# Board2.net
KiCad netlist of a schematic drawn in Altium Designer
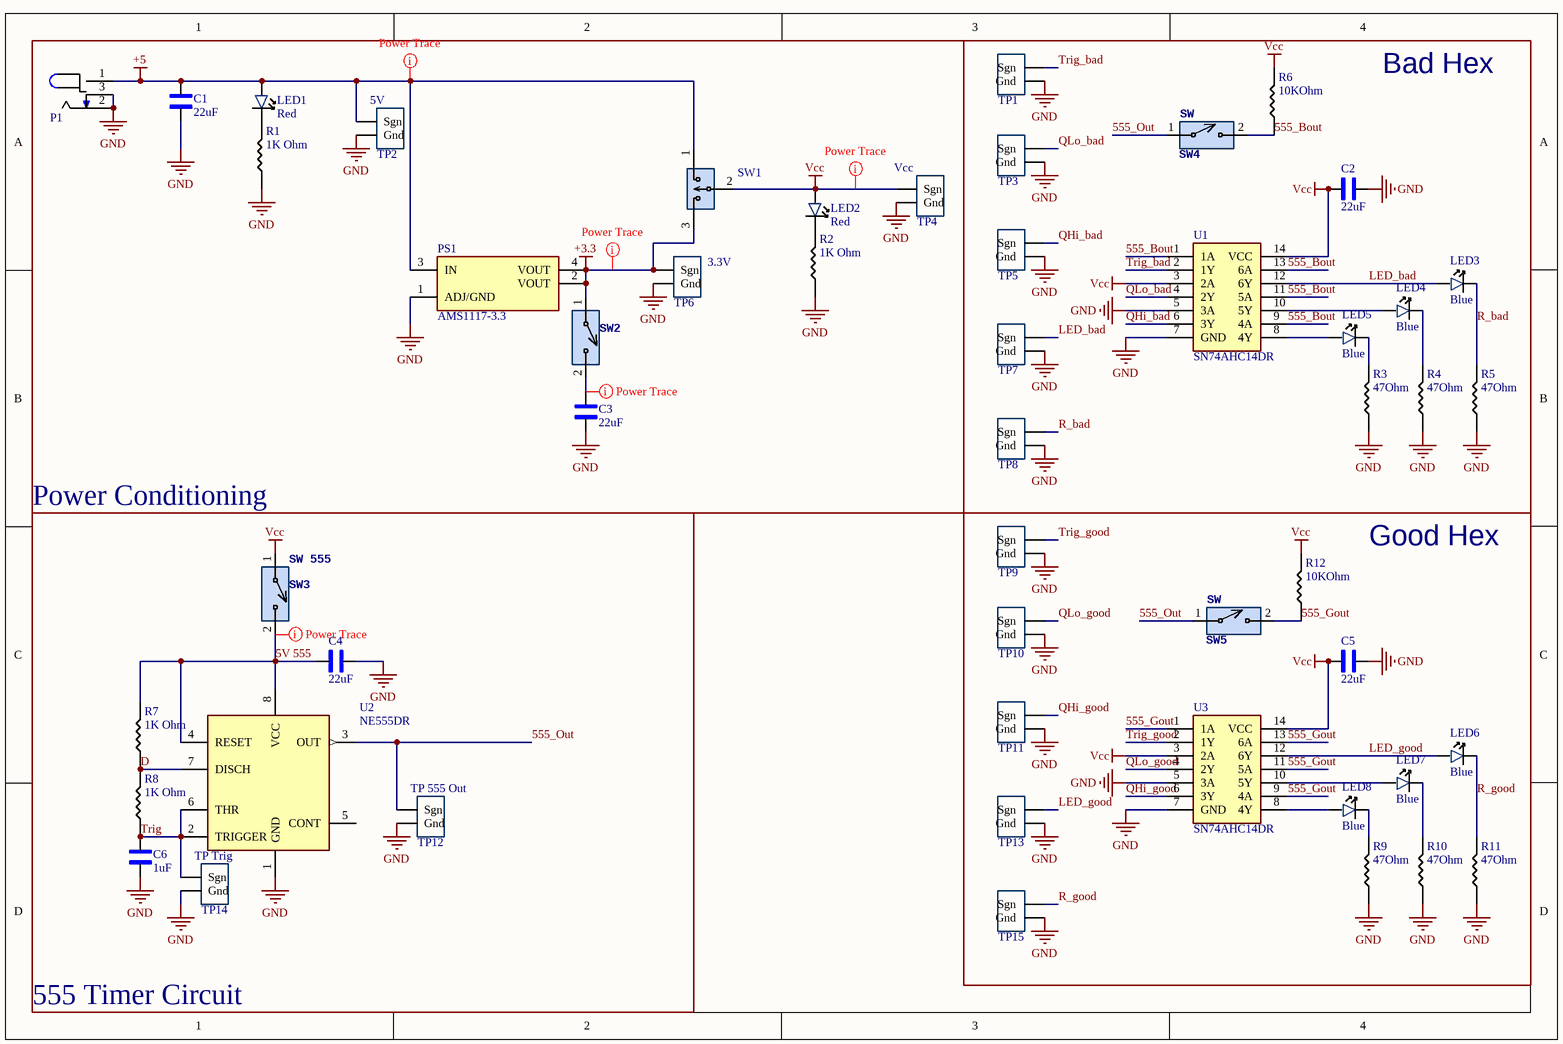
[diagram p0: Board2.SchDoc]

(export (version "E")
  (design (tool "Eeschema 10.0.6"))
  (components
    (comp (ref "C1")
      (value "22uF")
      (footprint "1206_Passive_Capacitor")
      (description "22uF ±10% 25V X5R 1206 Multilayer Ceramic Capacitors MLCC - SMD/SMT RoHS")
      (fields (field (name "MFR PART #") "CL31A226KAHNNNE") (field (name "LCSC PART#") "C12891"))
      (libsource (lib "ECEN5730Lib_2023_01_DS") (part "C_22uF_1206"))
    )
    (comp (ref "C2")
      (value "22uF")
      (footprint "1206_Passive_Capacitor")
      (description "22uF ±10% 25V X5R 1206 Multilayer Ceramic Capacitors MLCC - SMD/SMT RoHS")
      (fields (field (name "MFR PART #") "CL31A226KAHNNNE") (field (name "LCSC PART#") "C12891"))
      (libsource (lib "ECEN5730Lib_2023_01_DS") (part "C_22uF_1206"))
    )
    (comp (ref "C3")
      (value "22uF")
      (footprint "1206_Passive_Capacitor")
      (description "22uF ±10% 25V X5R 1206 Multilayer Ceramic Capacitors MLCC - SMD/SMT RoHS")
      (fields (field (name "MFR PART #") "CL31A226KAHNNNE") (field (name "LCSC PART#") "C12891"))
      (libsource (lib "ECEN5730Lib_2023_01_DS") (part "C_22uF_1206"))
    )
    (comp (ref "C4")
      (value "22uF")
      (footprint "1206_Passive_Capacitor")
      (description "22uF ±10% 25V X5R 1206 Multilayer Ceramic Capacitors MLCC - SMD/SMT RoHS")
      (fields (field (name "MFR PART #") "CL31A226KAHNNNE") (field (name "LCSC PART#") "C12891"))
      (libsource (lib "ECEN5730Lib_2023_01_DS") (part "C_22uF_1206"))
    )
    (comp (ref "C5")
      (value "22uF")
      (footprint "1206_Passive_Capacitor")
      (description "22uF ±10% 25V X5R 1206 Multilayer Ceramic Capacitors MLCC - SMD/SMT RoHS")
      (fields (field (name "MFR PART #") "CL31A226KAHNNNE") (field (name "LCSC PART#") "C12891"))
      (libsource (lib "ECEN5730Lib_2023_01_DS") (part "C_22uF_1206"))
    )
    (comp (ref "C6")
      (value "1uF")
      (footprint "1206_Passive_Capacitor")
      (description "MULTILAYER CERAMIC CAPACITORS MLCC - SMD/SMT 1UF 50V 1206 ROHS")
      (fields (field (name "MFR PART #") "CL31B105KBHNNNE") (field (name "LCSC PART#") "C1848"))
      (libsource (lib "ECEN5730Lib_2023_01_DS") (part "C_1uF_1206"))
    )
    (comp (ref "LED1")
      (value "Red")
      (footprint "LED_1206")
      (description "Red 621~631nm 1206 Light Emitting Diodes (LED) RoHS")
      (fields (field (name "MFR PART #") "15-21/R6C-FQ1R1B/2T") (field (name "LCSC PART#") "C93133"))
      (libsource (lib "ECEN5730Lib_2023_01_DS") (part "LED_RED_1206"))
    )
    (comp (ref "LED2")
      (value "Red")
      (footprint "LED_1206")
      (description "Red 621~631nm 1206 Light Emitting Diodes (LED) RoHS")
      (fields (field (name "MFR PART #") "15-21/R6C-FQ1R1B/2T") (field (name "LCSC PART#") "C93133"))
      (libsource (lib "ECEN5730Lib_2023_01_DS") (part "LED_RED_1206"))
    )
    (comp (ref "LED3")
      (value "Blue")
      (footprint "LED_1206")
      (description "blue 1206  Light Emitting Diodes (LED) ROHS")
      (fields (field (name "MFR PART #") "NCD1206B1") (field (name "LCSC PART#") "C130717"))
      (libsource (lib "ECEN5730Lib_2023_01_DS") (part "LED_BLUE_1206"))
    )
    (comp (ref "LED4")
      (value "Blue")
      (footprint "LED_1206")
      (description "blue 1206  Light Emitting Diodes (LED) ROHS")
      (fields (field (name "MFR PART #") "NCD1206B1") (field (name "LCSC PART#") "C130717"))
      (libsource (lib "ECEN5730Lib_2023_01_DS") (part "LED_BLUE_1206"))
    )
    (comp (ref "LED5")
      (value "Blue")
      (footprint "LED_1206")
      (description "blue 1206  Light Emitting Diodes (LED) ROHS")
      (fields (field (name "MFR PART #") "NCD1206B1") (field (name "LCSC PART#") "C130717"))
      (libsource (lib "ECEN5730Lib_2023_01_DS") (part "LED_BLUE_1206"))
    )
    (comp (ref "LED6")
      (value "Blue")
      (footprint "LED_1206")
      (description "blue 1206  Light Emitting Diodes (LED) ROHS")
      (fields (field (name "MFR PART #") "NCD1206B1") (field (name "LCSC PART#") "C130717"))
      (libsource (lib "ECEN5730Lib_2023_01_DS") (part "LED_BLUE_1206"))
    )
    (comp (ref "LED7")
      (value "Blue")
      (footprint "LED_1206")
      (description "blue 1206  Light Emitting Diodes (LED) ROHS")
      (fields (field (name "MFR PART #") "NCD1206B1") (field (name "LCSC PART#") "C130717"))
      (libsource (lib "ECEN5730Lib_2023_01_DS") (part "LED_BLUE_1206"))
    )
    (comp (ref "LED8")
      (value "Blue")
      (footprint "LED_1206")
      (description "blue 1206  Light Emitting Diodes (LED) ROHS")
      (fields (field (name "MFR PART #") "NCD1206B1") (field (name "LCSC PART#") "C130717"))
      (libsource (lib "ECEN5730Lib_2023_01_DS") (part "LED_BLUE_1206"))
    )
    (comp (ref "P1")
      (value "Power Jack")
      (footprint "Power_Jack")
      (description "Power Barrel Connector Jack 2.10mm ID (0.083\"), 5.50mm OD (0.217\") Through Hole, Right Angle")
      (fields (field (name "MFR PART #") "PJ-102A") (field (name "LCSC PART#") "C136744"))
      (libsource (lib "ECEN5730Lib_2023_01_DS") (part "P_Power Jack"))
    )
    (comp (ref "PS1")
      (value "AMS1117-3.3")
      (footprint "LDO")
      (description "LOW DROPOUT REGULATORS(LDO) POSITIVE FIXED 1.3V @ 800MA 15V 3.3V 1A SOT-223 ROHS")
      (fields (field (name "LCSC PART#") "C6186"))
      (libsource (lib "ECEN5730Lib_2023_01_DS") (part "PS_AMS_LDO_3v3"))
    )
    (comp (ref "R1")
      (value "1K Ohm")
      (footprint "1206_Passive_Resitor")
      (description "CHIP RESISTOR - SURFACE MOUNT 1KOHMS ±1% 1/4W 1206 ROHS")
      (fields (field (name "MFR PART #") "RNCP1206FTD1K00CT") (field (name "LCSC PART#") "C4410"))
      (libsource (lib "ECEN5730Lib_2023_01_DS") (part "R_1K_1206"))
    )
    (comp (ref "R2")
      (value "1K Ohm")
      (footprint "1206_Passive_Resitor")
      (description "CHIP RESISTOR - SURFACE MOUNT 1KOHMS ±1% 1/4W 1206 ROHS")
      (fields (field (name "MFR PART #") "RNCP1206FTD1K00CT") (field (name "LCSC PART#") "C4410"))
      (libsource (lib "ECEN5730Lib_2023_01_DS") (part "R_1K_1206"))
    )
    (comp (ref "R3")
      (value "47Ohm")
      (footprint "1206_Passive_Resitor")
      (description "47Ω ±5% 0.25W ±200ppm/℃ 1206 Chip Resistor - Surface Mount RoHS")
      (fields (field (name "MFR PART #") "1206W4J0470T5E") (field (name "LCSC PART#") "C25384"))
      (libsource (lib "ECEN5730Lib_2023_01_DS") (part "R_47Ohm_1206"))
    )
    (comp (ref "R4")
      (value "47Ohm")
      (footprint "1206_Passive_Resitor")
      (description "47Ω ±5% 0.25W ±200ppm/℃ 1206 Chip Resistor - Surface Mount RoHS")
      (fields (field (name "MFR PART #") "1206W4J0470T5E") (field (name "LCSC PART#") "C25384"))
      (libsource (lib "ECEN5730Lib_2023_01_DS") (part "R_47Ohm_1206"))
    )
    (comp (ref "R5")
      (value "47Ohm")
      (footprint "1206_Passive_Resitor")
      (description "47Ω ±5% 0.25W ±200ppm/℃ 1206 Chip Resistor - Surface Mount RoHS")
      (fields (field (name "MFR PART #") "1206W4J0470T5E") (field (name "LCSC PART#") "C25384"))
      (libsource (lib "ECEN5730Lib_2023_01_DS") (part "R_47Ohm_1206"))
    )
    (comp (ref "R6")
      (value "10KOhm")
      (footprint "1206_Passive_Resitor")
      (description "10 kOhms ±5% 0.25W, 1/4W Chip Resistor 1206 (3216 Metric) Automotive AEC-Q200 Thick Film")
      (fields (field (name "MFR PART #") "RMCF1206FT10K0") (field (name "LCSC PART#") "C17902"))
      (libsource (lib "ECEN5730Lib_2023_01_DS") (part "R_10KOhm_1206"))
    )
    (comp (ref "R7")
      (value "1K Ohm")
      (footprint "1206_Passive_Resitor")
      (description "CHIP RESISTOR - SURFACE MOUNT 1KOHMS ±1% 1/4W 1206 ROHS")
      (fields (field (name "MFR PART #") "RNCP1206FTD1K00CT") (field (name "LCSC PART#") "C4410"))
      (libsource (lib "ECEN5730Lib_2023_01_DS") (part "R_1K_1206"))
    )
    (comp (ref "R8")
      (value "1K Ohm")
      (footprint "1206_Passive_Resitor")
      (description "CHIP RESISTOR - SURFACE MOUNT 1KOHMS ±1% 1/4W 1206 ROHS")
      (fields (field (name "MFR PART #") "RNCP1206FTD1K00CT") (field (name "LCSC PART#") "C4410"))
      (libsource (lib "ECEN5730Lib_2023_01_DS") (part "R_1K_1206"))
    )
    (comp (ref "R9")
      (value "47Ohm")
      (footprint "1206_Passive_Resitor")
      (description "47Ω ±5% 0.25W ±200ppm/℃ 1206 Chip Resistor - Surface Mount RoHS")
      (fields (field (name "MFR PART #") "1206W4J0470T5E") (field (name "LCSC PART#") "C25384"))
      (libsource (lib "ECEN5730Lib_2023_01_DS") (part "R_47Ohm_1206"))
    )
    (comp (ref "R10")
      (value "47Ohm")
      (footprint "1206_Passive_Resitor")
      (description "47Ω ±5% 0.25W ±200ppm/℃ 1206 Chip Resistor - Surface Mount RoHS")
      (fields (field (name "MFR PART #") "1206W4J0470T5E") (field (name "LCSC PART#") "C25384"))
      (libsource (lib "ECEN5730Lib_2023_01_DS") (part "R_47Ohm_1206"))
    )
    (comp (ref "R11")
      (value "47Ohm")
      (footprint "1206_Passive_Resitor")
      (description "47Ω ±5% 0.25W ±200ppm/℃ 1206 Chip Resistor - Surface Mount RoHS")
      (fields (field (name "MFR PART #") "1206W4J0470T5E") (field (name "LCSC PART#") "C25384"))
      (libsource (lib "ECEN5730Lib_2023_01_DS") (part "R_47Ohm_1206"))
    )
    (comp (ref "R12")
      (value "10KOhm")
      (footprint "1206_Passive_Resitor")
      (description "10 kOhms ±5% 0.25W, 1/4W Chip Resistor 1206 (3216 Metric) Automotive AEC-Q200 Thick Film")
      (fields (field (name "MFR PART #") "RMCF1206FT10K0") (field (name "LCSC PART#") "C17902"))
      (libsource (lib "ECEN5730Lib_2023_01_DS") (part "R_10KOhm_1206"))
    )
    (comp (ref "SW1")
      (value "PREC003SAAN-RC")
      (footprint "3_PIN_100mil")
      (description "Connector Header Through Hole 3 position 0.100\" (2.54mm)")
      (fields (field (name "LCSC PART#") "C49257"))
      (libsource (lib "ECEN5730Lib_2023_01_DS") (part "SW_3Pin_100mil_Switch"))
    )
    (comp (ref "SW2")
      (value "SW_2Pin_100mil_Switch")
      (footprint "2Pin-Header-Conn")
      (description "2Pin Header")
      (fields (field (name "LCSC PART#") "C124375"))
      (libsource (lib "") (part "SW_2Pin_100mil_Switch_1"))
    )
    (comp (ref "SW3")
      (value "SW 555")
      (footprint "2Pin-Header-Conn")
      (description "2Pin Header")
      (fields (field (name "LCSC PART#") "C124375"))
      (libsource (lib "") (part "SW_2Pin_100mil_Switch_1"))
    )
    (comp (ref "SW4")
      (value "SW")
      (footprint "2Pin-Header-Conn")
      (description "2Pin Header")
      (fields (field (name "LCSC PART#") "C124375"))
      (libsource (lib "ECEN5730Lib_2023_01_DS") (part "SW_2Pin_100mil_Switch"))
    )
    (comp (ref "SW5")
      (value "SW")
      (footprint "2Pin-Header-Conn")
      (description "2Pin Header")
      (fields (field (name "LCSC PART#") "C124375"))
      (libsource (lib "ECEN5730Lib_2023_01_DS") (part "SW_2Pin_100mil_Switch"))
    )
    (comp (ref "TP1")
      (value "10x Probe TP")
      (footprint "TP10x_Probe")
      (description "Test Point 300 mil centers")
      (libsource (lib "") (part "TP_10x_Probe_1"))
    )
    (comp (ref "TP2")
      (value "5V")
      (footprint "TP10x_Probe")
      (description "Test Point 300 mil centers")
      (libsource (lib "ECEN5730Lib_2023_01_DS") (part "TP_10x_Probe"))
    )
    (comp (ref "TP3")
      (value "10x Probe TP")
      (footprint "TP10x_Probe")
      (description "Test Point 300 mil centers")
      (libsource (lib "") (part "TP_10x_Probe_1"))
    )
    (comp (ref "TP4")
      (value "Vcc")
      (footprint "TP10x_Probe")
      (description "Test Point 300 mil centers")
      (libsource (lib "ECEN5730Lib_2023_01_DS") (part "TP_10x_Probe"))
    )
    (comp (ref "TP5")
      (value "10x Probe TP")
      (footprint "TP10x_Probe")
      (description "Test Point 300 mil centers")
      (libsource (lib "") (part "TP_10x_Probe_1"))
    )
    (comp (ref "TP6")
      (value "3.3V")
      (footprint "TP10x_Probe")
      (description "Test Point 300 mil centers")
      (libsource (lib "ECEN5730Lib_2023_01_DS") (part "TP_10x_Probe"))
    )
    (comp (ref "TP7")
      (value "10x Probe TP")
      (footprint "TP10x_Probe")
      (description "Test Point 300 mil centers")
      (libsource (lib "") (part "TP_10x_Probe_1"))
    )
    (comp (ref "TP8")
      (value "10x Probe TP")
      (footprint "TP10x_Probe")
      (description "Test Point 300 mil centers")
      (libsource (lib "") (part "TP_10x_Probe_1"))
    )
    (comp (ref "TP9")
      (value "10x Probe TP")
      (footprint "TP10x_Probe")
      (description "Test Point 300 mil centers")
      (libsource (lib "") (part "TP_10x_Probe_1"))
    )
    (comp (ref "TP10")
      (value "10x Probe TP")
      (footprint "TP10x_Probe")
      (description "Test Point 300 mil centers")
      (libsource (lib "") (part "TP_10x_Probe_1"))
    )
    (comp (ref "TP11")
      (value "10x Probe TP")
      (footprint "TP10x_Probe")
      (description "Test Point 300 mil centers")
      (libsource (lib "") (part "TP_10x_Probe_1"))
    )
    (comp (ref "TP12")
      (value "TP 555 Out")
      (footprint "TP10x_Probe")
      (description "Test Point 300 mil centers")
      (libsource (lib "ECEN5730Lib_2023_01_DS") (part "TP_10x_Probe"))
    )
    (comp (ref "TP13")
      (value "10x Probe TP")
      (footprint "TP10x_Probe")
      (description "Test Point 300 mil centers")
      (libsource (lib "") (part "TP_10x_Probe_1"))
    )
    (comp (ref "TP14")
      (value "TP Trig")
      (footprint "TP10x_Probe")
      (description "Test Point 300 mil centers")
      (libsource (lib "ECEN5730Lib_2023_01_DS") (part "TP_10x_Probe"))
    )
    (comp (ref "TP15")
      (value "10x Probe TP")
      (footprint "TP10x_Probe")
      (description "Test Point 300 mil centers")
      (libsource (lib "") (part "TP_10x_Probe_1"))
    )
    (comp (ref "U1")
      (value "SN74AHC14DR")
      (footprint "HEX_74AC14")
      (description "Inverter IC 6 Channel Schmitt Trigger 14-SOIC")
      (fields (field (name "LCSC PART#") "C6942"))
      (libsource (lib "ECEN5730Lib_2023_01_DS") (part "U_74_AHC_Hex"))
    )
    (comp (ref "U2")
      (value "NE555DR")
      (footprint "TS555IDTTR")
      (description "555 Timer SOIC-8_150MIL ROHS 150ns Rise Time")
      (fields (field (name "LCSC PART#") "C7593"))
      (libsource (lib "ECEN5730Lib_2023_01_DS") (part "U_555_Slow"))
    )
    (comp (ref "U3")
      (value "SN74AHC14DR")
      (footprint "HEX_74AC14")
      (description "Inverter IC 6 Channel Schmitt Trigger 14-SOIC")
      (fields (field (name "LCSC PART#") "C6942"))
      (libsource (lib "ECEN5730Lib_2023_01_DS") (part "U_74_AHC_Hex"))
    )
  )
  (nets
    (net (code "1") (name "+3.3") (class "Default")
      (node (ref "PS1") (pin "2") (pinfunction "VOUT_2") (pintype "power_in"))
      (node (ref "PS1") (pin "4") (pinfunction "VOUT_4") (pintype "power_in"))
      (node (ref "SW1") (pin "3") (pinfunction "3_3") (pintype "passive"))
      (node (ref "SW2") (pin "1") (pinfunction "1_1") (pintype "passive"))
      (node (ref "TP6") (pin "1") (pinfunction "Sgn_1") (pintype "passive"))
    )
    (net (code "2") (name "+5") (class "Default")
      (node (ref "C1") (pin "2") (pinfunction "2_2") (pintype "passive"))
      (node (ref "LED1") (pin "1") (pinfunction "1_1") (pintype "passive"))
      (node (ref "P1") (pin "1") (pinfunction "1_1") (pintype "power_in"))
      (node (ref "PS1") (pin "3") (pinfunction "IN_3") (pintype "power_in"))
      (node (ref "SW1") (pin "1") (pinfunction "1_1") (pintype "passive"))
      (node (ref "TP2") (pin "1") (pinfunction "Sgn_1") (pintype "passive"))
    )
    (net (code "3") (name "/5V 555") (class "Default")
      (node (ref "C4") (pin "2") (pinfunction "2_2") (pintype "passive"))
      (node (ref "R7") (pin "2") (pinfunction "2_2") (pintype "passive"))
      (node (ref "SW3") (pin "2") (pinfunction "2_2") (pintype "passive"))
      (node (ref "U2") (pin "4") (pinfunction "RESET_4") (pintype "passive"))
      (node (ref "U2") (pin "8") (pinfunction "VCC_8") (pintype "power_in"))
    )
    (net (code "4") (name "/555_Bout") (class "Default")
      (node (ref "R6") (pin "1") (pinfunction "1_1") (pintype "passive"))
      (node (ref "SW4") (pin "2") (pinfunction "2_2") (pintype "passive"))
      (node (ref "U1") (pin "1") (pinfunction "1A_1") (pintype "passive"))
      (node (ref "U1") (pin "11") (pinfunction "5A_11") (pintype "passive"))
      (node (ref "U1") (pin "13") (pinfunction "6A_13") (pintype "passive"))
      (node (ref "U1") (pin "9") (pinfunction "4A_9") (pintype "passive"))
    )
    (net (code "5") (name "/555_Gout") (class "Default")
      (node (ref "R12") (pin "1") (pinfunction "1_1") (pintype "passive"))
      (node (ref "SW5") (pin "2") (pinfunction "2_2") (pintype "passive"))
      (node (ref "U3") (pin "1") (pinfunction "1A_1") (pintype "passive"))
      (node (ref "U3") (pin "11") (pinfunction "5A_11") (pintype "passive"))
      (node (ref "U3") (pin "13") (pinfunction "6A_13") (pintype "passive"))
      (node (ref "U3") (pin "9") (pinfunction "4A_9") (pintype "passive"))
    )
    (net (code "6") (name "/555_Out") (class "Default")
      (node (ref "SW4") (pin "1") (pinfunction "1_1") (pintype "passive"))
      (node (ref "SW5") (pin "1") (pinfunction "1_1") (pintype "passive"))
      (node (ref "TP12") (pin "1") (pinfunction "Sgn_1") (pintype "passive"))
      (node (ref "U2") (pin "3") (pinfunction "OUT_3") (pintype "output"))
    )
    (net (code "8") (name "/D") (class "Default")
      (node (ref "R7") (pin "1") (pinfunction "1_1") (pintype "passive"))
      (node (ref "R8") (pin "2") (pinfunction "2_2") (pintype "passive"))
      (node (ref "U2") (pin "7") (pinfunction "DISCH_7") (pintype "passive"))
    )
    (net (code "9") (name "/LED_bad") (class "Default")
      (node (ref "LED3") (pin "1") (pinfunction "1_1") (pintype "passive"))
      (node (ref "TP7") (pin "1") (pinfunction "Sgn_1") (pintype "passive"))
      (node (ref "U1") (pin "12") (pinfunction "6Y_12") (pintype "passive"))
    )
    (net (code "10") (name "/LED_good") (class "Default")
      (node (ref "LED6") (pin "1") (pinfunction "1_1") (pintype "passive"))
      (node (ref "TP13") (pin "1") (pinfunction "Sgn_1") (pintype "passive"))
      (node (ref "U3") (pin "12") (pinfunction "6Y_12") (pintype "passive"))
    )
    (net (code "11") (name "/QHi_bad") (class "Default")
      (node (ref "TP5") (pin "1") (pinfunction "Sgn_1") (pintype "passive"))
      (node (ref "U1") (pin "6") (pinfunction "3Y_6") (pintype "passive"))
    )
    (net (code "12") (name "/QHi_good") (class "Default")
      (node (ref "TP11") (pin "1") (pinfunction "Sgn_1") (pintype "passive"))
      (node (ref "U3") (pin "6") (pinfunction "3Y_6") (pintype "passive"))
    )
    (net (code "13") (name "/QLo_bad") (class "Default")
      (node (ref "TP3") (pin "1") (pinfunction "Sgn_1") (pintype "passive"))
      (node (ref "U1") (pin "4") (pinfunction "2Y_4") (pintype "passive"))
    )
    (net (code "14") (name "/QLo_good") (class "Default")
      (node (ref "TP10") (pin "1") (pinfunction "Sgn_1") (pintype "passive"))
      (node (ref "U3") (pin "4") (pinfunction "2Y_4") (pintype "passive"))
    )
    (net (code "15") (name "/R_bad") (class "Default")
      (node (ref "LED3") (pin "2") (pinfunction "2_2") (pintype "passive"))
      (node (ref "R5") (pin "2") (pinfunction "2_2") (pintype "passive"))
      (node (ref "TP8") (pin "1") (pinfunction "Sgn_1") (pintype "passive"))
    )
    (net (code "16") (name "/R_good") (class "Default")
      (node (ref "LED6") (pin "2") (pinfunction "2_2") (pintype "passive"))
      (node (ref "R11") (pin "2") (pinfunction "2_2") (pintype "passive"))
      (node (ref "TP15") (pin "1") (pinfunction "Sgn_1") (pintype "passive"))
    )
    (net (code "17") (name "/Trig") (class "Default")
      (node (ref "C6") (pin "2") (pinfunction "2_2") (pintype "passive"))
      (node (ref "R8") (pin "1") (pinfunction "1_1") (pintype "passive"))
      (node (ref "TP14") (pin "1") (pinfunction "Sgn_1") (pintype "passive"))
      (node (ref "U2") (pin "2") (pinfunction "TRIGGER_2") (pintype "passive"))
      (node (ref "U2") (pin "6") (pinfunction "THR_6") (pintype "passive"))
    )
    (net (code "18") (name "/Trig_bad") (class "Default")
      (node (ref "TP1") (pin "1") (pinfunction "Sgn_1") (pintype "passive"))
      (node (ref "U1") (pin "2") (pinfunction "1Y_2") (pintype "passive"))
    )
    (net (code "19") (name "/Trig_good") (class "Default")
      (node (ref "TP9") (pin "1") (pinfunction "Sgn_1") (pintype "passive"))
      (node (ref "U3") (pin "2") (pinfunction "1Y_2") (pintype "passive"))
    )
    (net (code "20") (name "GND") (class "Default")
      (node (ref "C1") (pin "1") (pinfunction "1_1") (pintype "passive"))
      (node (ref "C2") (pin "2") (pinfunction "2_2") (pintype "passive"))
      (node (ref "C3") (pin "1") (pinfunction "1_1") (pintype "passive"))
      (node (ref "C4") (pin "1") (pinfunction "1_1") (pintype "passive"))
      (node (ref "C5") (pin "2") (pinfunction "2_2") (pintype "passive"))
      (node (ref "C6") (pin "1") (pinfunction "1_1") (pintype "passive"))
      (node (ref "P1") (pin "2") (pinfunction "2_2") (pintype "power_in"))
      (node (ref "P1") (pin "3") (pinfunction "3_3") (pintype "power_in"))
      (node (ref "PS1") (pin "1") (pinfunction "ADJ/GND_1") (pintype "passive"))
      (node (ref "R1") (pin "1") (pinfunction "1_1") (pintype "passive"))
      (node (ref "R10") (pin "1") (pinfunction "1_1") (pintype "passive"))
      (node (ref "R11") (pin "1") (pinfunction "1_1") (pintype "passive"))
      (node (ref "R2") (pin "1") (pinfunction "1_1") (pintype "passive"))
      (node (ref "R3") (pin "1") (pinfunction "1_1") (pintype "passive"))
      (node (ref "R4") (pin "1") (pinfunction "1_1") (pintype "passive"))
      (node (ref "R5") (pin "1") (pinfunction "1_1") (pintype "passive"))
      (node (ref "R9") (pin "1") (pinfunction "1_1") (pintype "passive"))
      (node (ref "TP1") (pin "2") (pinfunction "Gnd_2") (pintype "passive"))
      (node (ref "TP10") (pin "2") (pinfunction "Gnd_2") (pintype "passive"))
      (node (ref "TP11") (pin "2") (pinfunction "Gnd_2") (pintype "passive"))
      (node (ref "TP12") (pin "2") (pinfunction "Gnd_2") (pintype "passive"))
      (node (ref "TP13") (pin "2") (pinfunction "Gnd_2") (pintype "passive"))
      (node (ref "TP14") (pin "2") (pinfunction "Gnd_2") (pintype "passive"))
      (node (ref "TP15") (pin "2") (pinfunction "Gnd_2") (pintype "passive"))
      (node (ref "TP2") (pin "2") (pinfunction "Gnd_2") (pintype "passive"))
      (node (ref "TP3") (pin "2") (pinfunction "Gnd_2") (pintype "passive"))
      (node (ref "TP4") (pin "2") (pinfunction "Gnd_2") (pintype "passive"))
      (node (ref "TP5") (pin "2") (pinfunction "Gnd_2") (pintype "passive"))
      (node (ref "TP6") (pin "2") (pinfunction "Gnd_2") (pintype "passive"))
      (node (ref "TP7") (pin "2") (pinfunction "Gnd_2") (pintype "passive"))
      (node (ref "TP8") (pin "2") (pinfunction "Gnd_2") (pintype "passive"))
      (node (ref "TP9") (pin "2") (pinfunction "Gnd_2") (pintype "passive"))
      (node (ref "U1") (pin "5") (pinfunction "3A_5") (pintype "passive"))
      (node (ref "U1") (pin "7") (pinfunction "GND_7") (pintype "passive"))
      (node (ref "U2") (pin "1") (pinfunction "GND_1") (pintype "power_in"))
      (node (ref "U3") (pin "5") (pinfunction "3A_5") (pintype "passive"))
      (node (ref "U3") (pin "7") (pinfunction "GND_7") (pintype "passive"))
    )
    (net (code "21") (name "Net-(C3-Pad2)") (class "Default")
      (node (ref "C3") (pin "2") (pinfunction "2_2") (pintype "passive"))
      (node (ref "SW2") (pin "2") (pinfunction "2_2") (pintype "passive"))
    )
    (net (code "22") (name "Net-(LED1-Pad2)") (class "Default")
      (node (ref "LED1") (pin "2") (pinfunction "2_2") (pintype "passive"))
      (node (ref "R1") (pin "2") (pinfunction "2_2") (pintype "passive"))
    )
    (net (code "23") (name "Net-(LED2-Pad2)") (class "Default")
      (node (ref "LED2") (pin "2") (pinfunction "2_2") (pintype "passive"))
      (node (ref "R2") (pin "2") (pinfunction "2_2") (pintype "passive"))
    )
    (net (code "24") (name "Net-(LED4-Pad2)") (class "Default")
      (node (ref "LED4") (pin "2") (pinfunction "2_2") (pintype "passive"))
      (node (ref "R4") (pin "2") (pinfunction "2_2") (pintype "passive"))
    )
    (net (code "25") (name "Net-(LED5-Pad2)") (class "Default")
      (node (ref "LED5") (pin "2") (pinfunction "2_2") (pintype "passive"))
      (node (ref "R3") (pin "2") (pinfunction "2_2") (pintype "passive"))
    )
    (net (code "26") (name "Net-(LED7-Pad2)") (class "Default")
      (node (ref "LED7") (pin "2") (pinfunction "2_2") (pintype "passive"))
      (node (ref "R10") (pin "2") (pinfunction "2_2") (pintype "passive"))
    )
    (net (code "27") (name "Net-(LED8-Pad2)") (class "Default")
      (node (ref "LED8") (pin "2") (pinfunction "2_2") (pintype "passive"))
      (node (ref "R9") (pin "2") (pinfunction "2_2") (pintype "passive"))
    )
    (net (code "28") (name "Net-(U1-4Y)") (class "Default")
      (node (ref "LED5") (pin "1") (pinfunction "1_1") (pintype "passive"))
      (node (ref "U1") (pin "8") (pinfunction "4Y_8") (pintype "passive"))
    )
    (net (code "29") (name "Net-(U1-5Y)") (class "Default")
      (node (ref "LED4") (pin "1") (pinfunction "1_1") (pintype "passive"))
      (node (ref "U1") (pin "10") (pinfunction "5Y_10") (pintype "passive"))
    )
    (net (code "30") (name "Net-(U3-4Y)") (class "Default")
      (node (ref "LED8") (pin "1") (pinfunction "1_1") (pintype "passive"))
      (node (ref "U3") (pin "8") (pinfunction "4Y_8") (pintype "passive"))
    )
    (net (code "31") (name "Net-(U3-5Y)") (class "Default")
      (node (ref "LED7") (pin "1") (pinfunction "1_1") (pintype "passive"))
      (node (ref "U3") (pin "10") (pinfunction "5Y_10") (pintype "passive"))
    )
    (net (code "32") (name "Vcc") (class "Default")
      (node (ref "C2") (pin "1") (pinfunction "1_1") (pintype "passive"))
      (node (ref "C5") (pin "1") (pinfunction "1_1") (pintype "passive"))
      (node (ref "LED2") (pin "1") (pinfunction "1_1") (pintype "passive"))
      (node (ref "R12") (pin "2") (pinfunction "2_2") (pintype "passive"))
      (node (ref "R6") (pin "2") (pinfunction "2_2") (pintype "passive"))
      (node (ref "SW1") (pin "2") (pinfunction "2_2") (pintype "passive"))
      (node (ref "SW3") (pin "1") (pinfunction "1_1") (pintype "passive"))
      (node (ref "TP4") (pin "1") (pinfunction "Sgn_1") (pintype "passive"))
      (node (ref "U1") (pin "14") (pinfunction "VCC_14") (pintype "passive"))
      (node (ref "U1") (pin "3") (pinfunction "2A_3") (pintype "passive"))
      (node (ref "U3") (pin "14") (pinfunction "VCC_14") (pintype "passive"))
      (node (ref "U3") (pin "3") (pinfunction "2A_3") (pintype "passive"))
    )
    (net (code "33") (name "unconnected-(U2-CONT-Pad5)") (class "Default")
      (node (ref "U2") (pin "5") (pinfunction "CONT_5") (pintype "passive"))
    )
  )
)
